# MotorMCU.net
KiCad netlist of a schematic drawn in Altium Designer
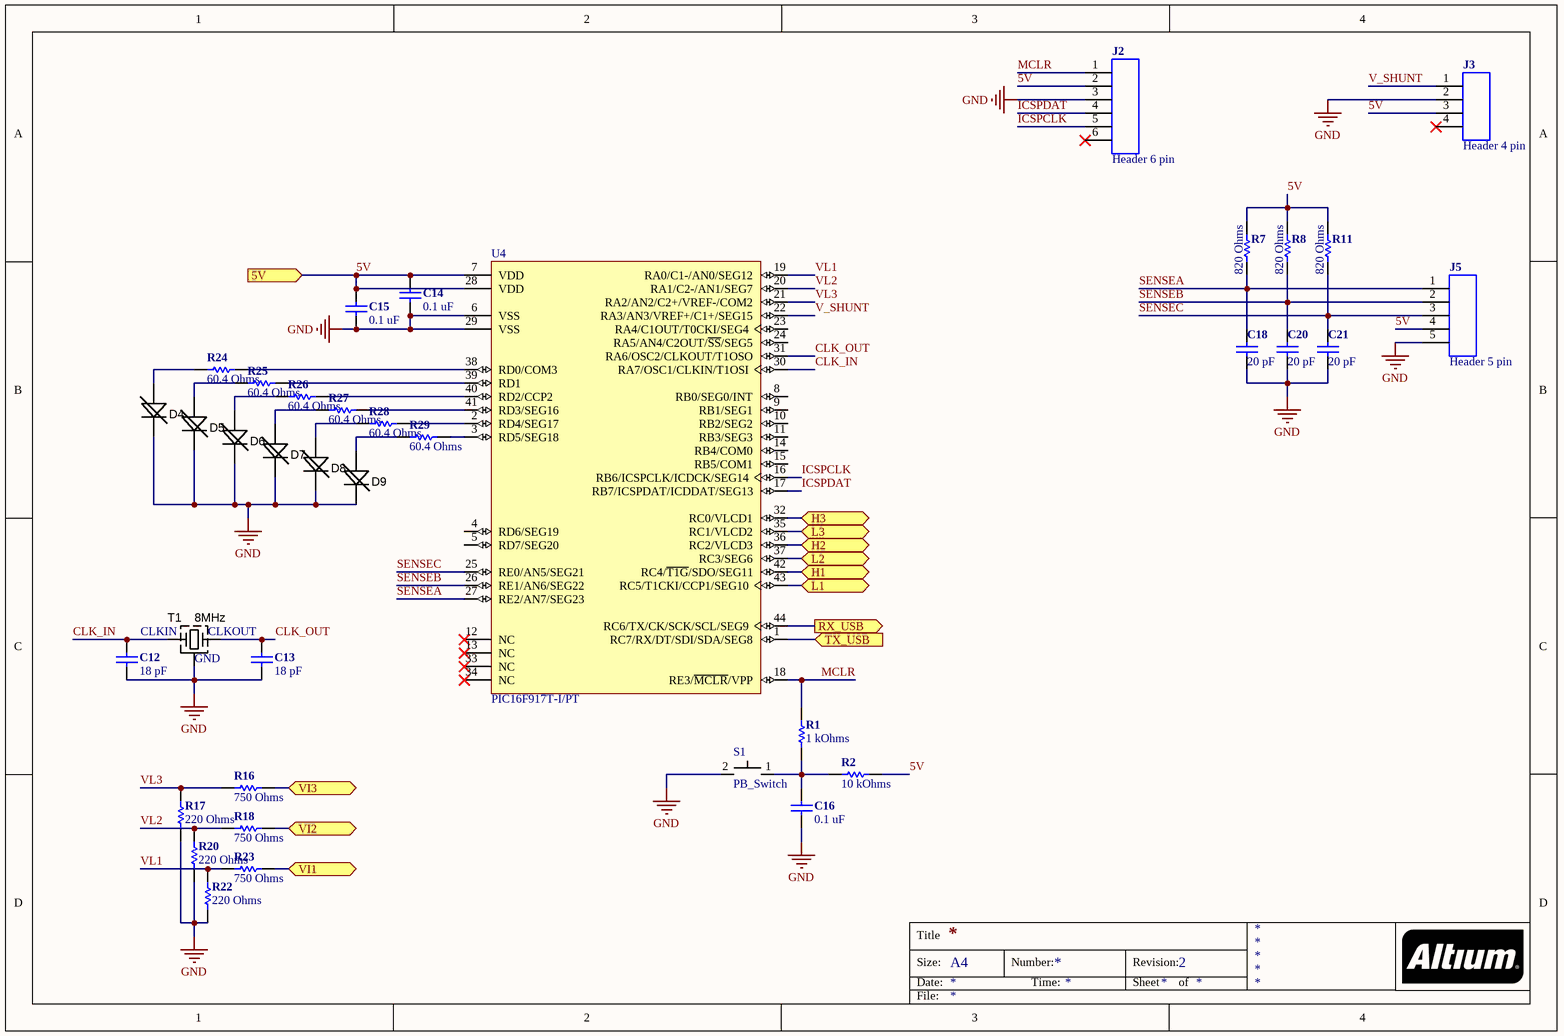
[diagram p0: MotorMCU.SchDoc]

(export (version "E")
  (design (tool "Eeschema 10.0.6"))
  (components
    (comp (ref "C12")
      (value "18 pF")
      (footprint "CAP-0603(1608)-R")
      (description "CAP CER 18 pF 10V 5% C0G 0603")
      (fields (field (name "TOLERANCE") "1 %") (field (name "MANUFACTURER") "Yageo"))
      (libsource (lib "CarlLibrary") (part "CAP- 18 pF- 25 V-CER-0603(1608)"))
    )
    (comp (ref "C13")
      (value "18 pF")
      (footprint "CAP-0603(1608)-R")
      (description "CAP CER 18 pF 10V 5% C0G 0603")
      (fields (field (name "TOLERANCE") "1 %") (field (name "MANUFACTURER") "Yageo"))
      (libsource (lib "CarlLibrary") (part "CAP- 18 pF- 25 V-CER-0603(1608)"))
    )
    (comp (ref "C14")
      (value "0.1 uF")
      (footprint "CAP-0402(1005)-R")
      (description "CAP CER 0.1 UF 16V 5% X7R 0402")
      (fields
        (field (name "MANUFACTURER") "Yageo")
        (field (name "MANUFACTURER PART NUMBER") "CC0402KRX7R7BB104")
      )
      (libsource (lib "CarlLibrary") (part "CAP- 0.1 uF- 16 V-CER-0402(1005)"))
    )
    (comp (ref "C15")
      (value "0.1 uF")
      (footprint "CAP-0402(1005)-R")
      (description "CAP CER 0.1 UF 16V 5% X7R 0402")
      (fields
        (field (name "MANUFACTURER") "Yageo")
        (field (name "MANUFACTURER PART NUMBER") "CC0402KRX7R7BB104")
      )
      (libsource (lib "CarlLibrary") (part "CAP- 0.1 uF- 16 V-CER-0402(1005)"))
    )
    (comp (ref "C16")
      (value "0.1 uF")
      (footprint "CAP-0402(1005)-R")
      (description "CAP CER 0.1 UF 16V 5% X7R 0402")
      (fields (field (name "TOLERANCE") "10 %") (field (name "MANUFACTURER") "Yageo"))
      (libsource (lib "CarlLibrary") (part "CAP- 0.1 uF- 16 V-CER-0402(1005)"))
    )
    (comp (ref "C18")
      (value "20 pF")
      (footprint "CAP-0402(1005)-R")
      (description "CAP CER 20 pF 50V 5% C0G 0402")
      (fields (field (name "TOLERANCE") "5 %") (field (name "MANUFACTURER") "Yageo"))
      (libsource (lib "CarlLibrary") (part "CAP- 20 pF- 50 V-CER-0402(1005)"))
    )
    (comp (ref "C20")
      (value "20 pF")
      (footprint "CAP-0402(1005)-R")
      (description "CAP CER 20 pF 50V 5% C0G 0402")
      (fields (field (name "TOLERANCE") "5 %") (field (name "MANUFACTURER") "Yageo"))
      (libsource (lib "CarlLibrary") (part "CAP- 20 pF- 50 V-CER-0402(1005)"))
    )
    (comp (ref "C21")
      (value "20 pF")
      (footprint "CAP-0402(1005)-R")
      (description "CAP CER 20 pF 50V 5% C0G 0402")
      (fields (field (name "TOLERANCE") "5 %") (field (name "MANUFACTURER") "Yageo"))
      (libsource (lib "CarlLibrary") (part "CAP- 20 pF- 50 V-CER-0402(1005)"))
    )
    (comp (ref "D4")
      (value "Red")
      (footprint "LED-1206")
      (description "LED, 0805 SMD, Red")
      (fields
        (field (name "MANUFACTURER") "Kingbright")
        (field (name "MANUFACTURER PART NUMBER") "APTD3216SURCK")
      )
      (libsource (lib "CarlLibrary") (part "LED_SMD_RED_0805"))
    )
    (comp (ref "D5")
      (value "Red")
      (footprint "LED-1206")
      (description "LED, 0805 SMD, Red")
      (fields
        (field (name "MANUFACTURER") "Kingbright")
        (field (name "MANUFACTURER PART NUMBER") "APTD3216SURCK")
      )
      (libsource (lib "CarlLibrary") (part "LED_SMD_RED_0805"))
    )
    (comp (ref "D6")
      (value "Red")
      (footprint "LED-1206")
      (description "LED, 0805 SMD, Red")
      (fields
        (field (name "MANUFACTURER") "Kingbright")
        (field (name "MANUFACTURER PART NUMBER") "APTD3216SURCK")
      )
      (libsource (lib "CarlLibrary") (part "LED_SMD_RED_0805"))
    )
    (comp (ref "D7")
      (value "Red")
      (footprint "LED-1206")
      (description "LED, 0805 SMD, Red")
      (fields
        (field (name "MANUFACTURER") "Kingbright")
        (field (name "MANUFACTURER PART NUMBER") "APTD3216SURCK")
      )
      (libsource (lib "CarlLibrary") (part "LED_SMD_RED_0805"))
    )
    (comp (ref "D8")
      (value "Red")
      (footprint "LED-1206")
      (description "LED, 0805 SMD, Red")
      (fields
        (field (name "MANUFACTURER") "Kingbright")
        (field (name "MANUFACTURER PART NUMBER") "APTD3216SURCK")
      )
      (libsource (lib "CarlLibrary") (part "LED_SMD_RED_0805"))
    )
    (comp (ref "D9")
      (value "Red")
      (footprint "LED-1206")
      (description "LED, 0805 SMD, Red")
      (fields
        (field (name "MANUFACTURER") "Kingbright")
        (field (name "MANUFACTURER PART NUMBER") "APTD3216SURCK")
      )
      (libsource (lib "CarlLibrary") (part "LED_SMD_RED_0805"))
    )
    (comp (ref "J2")
      (value "Header 6 pin")
      (footprint "HEADER-6-100mil")
      (description "Header, 6 pin, .1 pitch")
      (fields
        (field (name "MANUFACTURER") "TE Connectivity / AMP")
        (field (name "MANUFACTURER PART NUMBER") "4-103327-6")
      )
      (libsource (lib "CarlLibrary") (part "CON-6Pin-100Mil"))
    )
    (comp (ref "J3")
      (value "Header 4 pin")
      (footprint "HEADER-4-100mil")
      (description "Header, 4 pin, .1 pitch")
      (fields (field (name "MANUFACTURER") "Molex") (field (name "MANUFACTURER PART NUMBER") "90136-1104"))
      (libsource (lib "CarlLibrary") (part "CON-4Pin-100Mil"))
    )
    (comp (ref "J5")
      (value "Header 5 pin")
      (footprint "HEADER-5-100mil")
      (description "Header, 5 pin, .1 pitch")
      (fields (field (name "MANUFACTURER") "Molex") (field (name "MANUFACTURER PART NUMBER") "90136-1105"))
      (libsource (lib "CarlLibrary") (part "CON-5Pin-100Mil"))
    )
    (comp (ref "R1")
      (value "1 kOhms")
      (footprint "R-0402(1005)-R")
      (description "RES 1K OHM 62.5 mW 0402(1005) SMD")
      (fields
        (field (name "MANUFACTURER") "Yageo")
        (field (name "MANUFACTURER PART NUMBER") "RC0402JR-071KL")
      )
      (libsource (lib "CarlLibrary") (part "R-1K-62.5 mW-0402(1005)"))
    )
    (comp (ref "R2")
      (value "10 kOhms")
      (footprint "R-0603(1608)-R")
      (description "RES 10k OHM 1/10W 0603 SMD")
      (fields
        (field (name "MANUFACTURER") "Yageo")
        (field (name "MANUFACTURER PART NUMBER") "RC0603FR-0710KL")
      )
      (libsource (lib "CarlLibrary") (part "R-10k-100mW-0603"))
    )
    (comp (ref "R7")
      (value "820 Ohms")
      (footprint "R-0603(1608)-R")
      (description "RES 820 OHM 100 mW 0603(1608) SMD")
      (fields
        (field (name "MANUFACTURER") "Yageo")
        (field (name "MANUFACTURER PART NUMBER") "RT0603DRD07820RL")
      )
      (libsource (lib "CarlLibrary") (part "R-820-100mW-0603(1608)"))
    )
    (comp (ref "R8")
      (value "820 Ohms")
      (footprint "R-0603(1608)-R")
      (description "RES 820 OHM 100 mW 0603(1608) SMD")
      (fields
        (field (name "MANUFACTURER") "Yageo")
        (field (name "MANUFACTURER PART NUMBER") "RT0603DRD07820RL")
      )
      (libsource (lib "CarlLibrary") (part "R-820-100mW-0603(1608)"))
    )
    (comp (ref "R11")
      (value "820 Ohms")
      (footprint "R-0603(1608)-R")
      (description "RES 820 OHM 100 mW 0603(1608) SMD")
      (fields
        (field (name "MANUFACTURER") "Yageo")
        (field (name "MANUFACTURER PART NUMBER") "RT0603DRD07820RL")
      )
      (libsource (lib "CarlLibrary") (part "R-820-100mW-0603(1608)"))
    )
    (comp (ref "R16")
      (value "750 Ohms")
      (footprint "R-0603(1608)-R")
      (description "RES 750 OHM 100 mW 0603(1608) SMD")
      (fields
        (field (name "MANUFACTURER") "Yageo")
        (field (name "MANUFACTURER PART NUMBER") "RT0603DRD07750RL")
      )
      (libsource (lib "CarlLibrary") (part "R-750-100mW-0603(1608)"))
    )
    (comp (ref "R17")
      (value "220 Ohms")
      (footprint "R-0603(1608)-R")
      (description "RES 220 OHM 100 mW 0603(1608) SMD")
      (fields
        (field (name "MANUFACTURER") "Yageo")
        (field (name "MANUFACTURER PART NUMBER") "RT0603FRE07220RL")
      )
      (libsource (lib "CarlLibrary") (part "R-220-100 mW-0603(1608)"))
    )
    (comp (ref "R18")
      (value "750 Ohms")
      (footprint "R-0603(1608)-R")
      (description "RES 750 OHM 100 mW 0603(1608) SMD")
      (fields
        (field (name "MANUFACTURER") "Yageo")
        (field (name "MANUFACTURER PART NUMBER") "RT0603DRD07750RL")
      )
      (libsource (lib "CarlLibrary") (part "R-750-100mW-0603(1608)"))
    )
    (comp (ref "R20")
      (value "220 Ohms")
      (footprint "R-0603(1608)-R")
      (description "RES 220 OHM 100 mW 0603(1608) SMD")
      (fields
        (field (name "MANUFACTURER") "Yageo")
        (field (name "MANUFACTURER PART NUMBER") "RT0603FRE07220RL")
      )
      (libsource (lib "CarlLibrary") (part "R-220-100 mW-0603(1608)"))
    )
    (comp (ref "R22")
      (value "220 Ohms")
      (footprint "R-0603(1608)-R")
      (description "RES 220 OHM 100 mW 0603(1608) SMD")
      (fields
        (field (name "MANUFACTURER") "Yageo")
        (field (name "MANUFACTURER PART NUMBER") "RT0603FRE07220RL")
      )
      (libsource (lib "CarlLibrary") (part "R-220-100 mW-0603(1608)"))
    )
    (comp (ref "R23")
      (value "750 Ohms")
      (footprint "R-0603(1608)-R")
      (description "RES 750 OHM 100 mW 0603(1608) SMD")
      (fields
        (field (name "MANUFACTURER") "Yageo")
        (field (name "MANUFACTURER PART NUMBER") "RT0603DRD07750RL")
      )
      (libsource (lib "CarlLibrary") (part "R-750-100mW-0603(1608)"))
    )
    (comp (ref "R24")
      (value "60.4 Ohms")
      (footprint "R-0603(1608)-R")
      (description "RES 60.4 OHM 100 mW  SMD")
      (fields
        (field (name "MANUFACTURER") "Yageo")
        (field (name "MANUFACTURER PART NUMBER") "RC0603FR-0760R4L")
      )
      (libsource (lib "CarlLibrary") (part "R-60.4-100mW-0805"))
    )
    (comp (ref "R25")
      (value "60.4 Ohms")
      (footprint "R-0603(1608)-R")
      (description "RES 60.4 OHM 100 mW  SMD")
      (fields
        (field (name "MANUFACTURER") "Yageo")
        (field (name "MANUFACTURER PART NUMBER") "RC0603FR-0760R4L")
      )
      (libsource (lib "CarlLibrary") (part "R-60.4-100mW-0805"))
    )
    (comp (ref "R26")
      (value "60.4 Ohms")
      (footprint "R-0603(1608)-R")
      (description "RES 60.4 OHM 100 mW  SMD")
      (fields
        (field (name "MANUFACTURER") "Yageo")
        (field (name "MANUFACTURER PART NUMBER") "RC0603FR-0760R4L")
      )
      (libsource (lib "CarlLibrary") (part "R-60.4-100mW-0805"))
    )
    (comp (ref "R27")
      (value "60.4 Ohms")
      (footprint "R-0603(1608)-R")
      (description "RES 60.4 OHM 100 mW  SMD")
      (fields
        (field (name "MANUFACTURER") "Yageo")
        (field (name "MANUFACTURER PART NUMBER") "RC0603FR-0760R4L")
      )
      (libsource (lib "CarlLibrary") (part "R-60.4-100mW-0805"))
    )
    (comp (ref "R28")
      (value "60.4 Ohms")
      (footprint "R-0603(1608)-R")
      (description "RES 60.4 OHM 100 mW  SMD")
      (fields
        (field (name "MANUFACTURER") "Yageo")
        (field (name "MANUFACTURER PART NUMBER") "RC0603FR-0760R4L")
      )
      (libsource (lib "CarlLibrary") (part "R-60.4-100mW-0805"))
    )
    (comp (ref "R29")
      (value "60.4 Ohms")
      (footprint "R-0603(1608)-R")
      (description "RES 60.4 OHM 100 mW  SMD")
      (fields
        (field (name "MANUFACTURER") "Yageo")
        (field (name "MANUFACTURER PART NUMBER") "RC0603FR-0760R4L")
      )
      (libsource (lib "CarlLibrary") (part "R-60.4-100mW-0805"))
    )
    (comp (ref "S1")
      (value "PB_Switch")
      (footprint "Pushbutton_switches")
      (fields
        (field (name "MANUFACTURER") "TE Connectivity / Alcoswitch")
        (field (name "MANUFACTURER PART NUMBER") "2-1437565-8")
      )
      (libsource (lib "MasterLibrary") (part "PB_Switch"))
    )
    (comp (ref "T1")
      (value "8MHz")
      (footprint "CRYSTAL-8MHZ")
      (description "Oscillator Crystal 8MHz 10ppm")
      (fields
        (field (name "MANUFACTURER") "ABRACON")
        (field (name "MANUFACTURER PART NUMBER") "ABMM2-8.000MHZ-E2-T")
      )
      (libsource (lib "CarlLibrary") (part "CRYSTAL_8MHz"))
    )
    (comp (ref "U4")
      (value "PIC16F917T-I/PT")
      (footprint "TQFP-44")
      (fields
        (field (name "MANUFACTURER") "Microchip Technology")
        (field (name "MANUFACTURER PART NUMBER") "PIC16F917-I/PT")
      )
      (libsource (lib "MasterLibrary") (part "PIC16F917"))
    )
  )
  (nets
    (net (code "1") (name "/5V") (class "Default")
      (node (ref "C14") (pin "1") (pinfunction "1_1") (pintype "passive"))
      (node (ref "C15") (pin "1") (pinfunction "1_1") (pintype "passive"))
      (node (ref "J2") (pin "2") (pinfunction "2_2") (pintype "passive"))
      (node (ref "J3") (pin "3") (pinfunction "3_3") (pintype "passive"))
      (node (ref "J5") (pin "4") (pinfunction "4_4") (pintype "passive"))
      (node (ref "R11") (pin "1") (pinfunction "1_1") (pintype "passive"))
      (node (ref "R2") (pin "2") (pinfunction "2_2") (pintype "passive"))
      (node (ref "R7") (pin "1") (pinfunction "1_1") (pintype "passive"))
      (node (ref "R8") (pin "1") (pinfunction "1_1") (pintype "passive"))
      (node (ref "U4") (pin "28") (pinfunction "VDD_28") (pintype "power_in"))
      (node (ref "U4") (pin "7") (pinfunction "VDD_7") (pintype "power_in"))
    )
    (net (code "2") (name "/CLK_IN") (class "Default")
      (node (ref "C12") (pin "1") (pinfunction "1_1") (pintype "passive"))
      (node (ref "T1") (pin "1") (pinfunction "CLKIN_1") (pintype "passive"))
      (node (ref "U4") (pin "30") (pinfunction "RA7/OSC1/CLKIN/T1OSI_30") (pintype "bidirectional"))
    )
    (net (code "3") (name "/CLK_OUT") (class "Default")
      (node (ref "C13") (pin "1") (pinfunction "1_1") (pintype "passive"))
      (node (ref "T1") (pin "3") (pinfunction "X_3") (pintype "passive"))
      (node (ref "U4") (pin "31") (pinfunction "RA6/OSC2/CLKOUT/T1OSO_31") (pintype "bidirectional"))
    )
    (net (code "4") (name "/H1") (class "Default")
      (node (ref "U4") (pin "42") (pinfunction "RC4/~{T1G}/SDO/SEG11_42") (pintype "bidirectional"))
    )
    (net (code "5") (name "/H2") (class "Default")
      (node (ref "U4") (pin "36") (pinfunction "RC2/VLCD3_36") (pintype "bidirectional"))
    )
    (net (code "6") (name "/H3") (class "Default")
      (node (ref "U4") (pin "32") (pinfunction "RC0/VLCD1_32") (pintype "bidirectional"))
    )
    (net (code "7") (name "/ICSPCLK") (class "Default")
      (node (ref "J2") (pin "5") (pinfunction "5_5") (pintype "passive"))
      (node (ref "U4") (pin "16") (pinfunction "RB6/ICSPCLK/ICDCK/SEG14_16") (pintype "bidirectional"))
    )
    (net (code "8") (name "/ICSPDAT") (class "Default")
      (node (ref "J2") (pin "4") (pinfunction "4_4") (pintype "passive"))
      (node (ref "U4") (pin "17") (pinfunction "RB7/ICSPDAT/ICDDAT/SEG13_17") (pintype "bidirectional"))
    )
    (net (code "9") (name "/L1") (class "Default")
      (node (ref "U4") (pin "43") (pinfunction "RC5/T1CKI/CCP1/SEG10_43") (pintype "bidirectional"))
    )
    (net (code "10") (name "/L2") (class "Default")
      (node (ref "U4") (pin "37") (pinfunction "RC3/SEG6_37") (pintype "bidirectional"))
    )
    (net (code "11") (name "/L3") (class "Default")
      (node (ref "U4") (pin "35") (pinfunction "RC1/VLCD2_35") (pintype "bidirectional"))
    )
    (net (code "12") (name "/MCLR") (class "Default")
      (node (ref "J2") (pin "1") (pinfunction "1_1") (pintype "passive"))
      (node (ref "R1") (pin "1") (pinfunction "1_1") (pintype "passive"))
      (node (ref "U4") (pin "18") (pinfunction "RE3/~{MCLR}/VPP_18") (pintype "bidirectional"))
    )
    (net (code "13") (name "/RX_USB") (class "Default")
      (node (ref "U4") (pin "44") (pinfunction "RC6/TX/CK/SCK/SCL/SEG9_44") (pintype "bidirectional"))
    )
    (net (code "14") (name "/SENSEA") (class "Default")
      (node (ref "C18") (pin "1") (pinfunction "1_1") (pintype "passive"))
      (node (ref "J5") (pin "1") (pinfunction "1_1") (pintype "passive"))
      (node (ref "R7") (pin "2") (pinfunction "2_2") (pintype "passive"))
      (node (ref "U4") (pin "27") (pinfunction "RE2/AN7/SEG23_27") (pintype "bidirectional"))
    )
    (net (code "15") (name "/SENSEB") (class "Default")
      (node (ref "C20") (pin "1") (pinfunction "1_1") (pintype "passive"))
      (node (ref "J5") (pin "2") (pinfunction "2_2") (pintype "passive"))
      (node (ref "R8") (pin "2") (pinfunction "2_2") (pintype "passive"))
      (node (ref "U4") (pin "26") (pinfunction "RE1/AN6/SEG22_26") (pintype "bidirectional"))
    )
    (net (code "16") (name "/SENSEC") (class "Default")
      (node (ref "C21") (pin "1") (pinfunction "1_1") (pintype "passive"))
      (node (ref "J5") (pin "3") (pinfunction "3_3") (pintype "passive"))
      (node (ref "R11") (pin "2") (pinfunction "2_2") (pintype "passive"))
      (node (ref "U4") (pin "25") (pinfunction "RE0/AN5/SEG21_25") (pintype "bidirectional"))
    )
    (net (code "17") (name "/TX_USB") (class "Default")
      (node (ref "U4") (pin "1") (pinfunction "RC7/RX/DT/SDI/SDA/SEG8_1") (pintype "bidirectional"))
    )
    (net (code "18") (name "/VI1") (class "Default")
      (node (ref "R23") (pin "2") (pinfunction "2_2") (pintype "passive"))
    )
    (net (code "19") (name "/VI2") (class "Default")
      (node (ref "R18") (pin "2") (pinfunction "2_2") (pintype "passive"))
    )
    (net (code "20") (name "/VI3") (class "Default")
      (node (ref "R16") (pin "2") (pinfunction "2_2") (pintype "passive"))
    )
    (net (code "21") (name "/VL1") (class "Default")
      (node (ref "R22") (pin "1") (pinfunction "1_1") (pintype "passive"))
      (node (ref "R23") (pin "1") (pinfunction "1_1") (pintype "passive"))
      (node (ref "U4") (pin "19") (pinfunction "RA0/C1-/AN0/SEG12_19") (pintype "bidirectional"))
    )
    (net (code "22") (name "/VL2") (class "Default")
      (node (ref "R18") (pin "1") (pinfunction "1_1") (pintype "passive"))
      (node (ref "R20") (pin "1") (pinfunction "1_1") (pintype "passive"))
      (node (ref "U4") (pin "20") (pinfunction "RA1/C2-/AN1/SEG7_20") (pintype "bidirectional"))
    )
    (net (code "23") (name "/VL3") (class "Default")
      (node (ref "R16") (pin "1") (pinfunction "1_1") (pintype "passive"))
      (node (ref "R17") (pin "1") (pinfunction "1_1") (pintype "passive"))
      (node (ref "U4") (pin "21") (pinfunction "RA2/AN2/C2+/VREF-/COM2_21") (pintype "bidirectional"))
    )
    (net (code "24") (name "/V_SHUNT") (class "Default")
      (node (ref "J3") (pin "1") (pinfunction "1_1") (pintype "passive"))
      (node (ref "U4") (pin "22") (pinfunction "RA3/AN3/VREF+/C1+/SEG15_22") (pintype "bidirectional"))
    )
    (net (code "25") (name "GND") (class "Default")
      (node (ref "C12") (pin "2") (pinfunction "2_2") (pintype "passive"))
      (node (ref "C13") (pin "2") (pinfunction "2_2") (pintype "passive"))
      (node (ref "C14") (pin "2") (pinfunction "2_2") (pintype "passive"))
      (node (ref "C15") (pin "2") (pinfunction "2_2") (pintype "passive"))
      (node (ref "C16") (pin "1") (pinfunction "1_1") (pintype "passive"))
      (node (ref "C18") (pin "2") (pinfunction "2_2") (pintype "passive"))
      (node (ref "C20") (pin "2") (pinfunction "2_2") (pintype "passive"))
      (node (ref "C21") (pin "2") (pinfunction "2_2") (pintype "passive"))
      (node (ref "D4") (pin "K") (pinfunction "K_K") (pintype "passive"))
      (node (ref "D5") (pin "K") (pinfunction "K_K") (pintype "passive"))
      (node (ref "D6") (pin "K") (pinfunction "K_K") (pintype "passive"))
      (node (ref "D7") (pin "K") (pinfunction "K_K") (pintype "passive"))
      (node (ref "D8") (pin "K") (pinfunction "K_K") (pintype "passive"))
      (node (ref "D9") (pin "K") (pinfunction "K_K") (pintype "passive"))
      (node (ref "J2") (pin "3") (pinfunction "3_3") (pintype "passive"))
      (node (ref "J3") (pin "2") (pinfunction "2_2") (pintype "passive"))
      (node (ref "J5") (pin "5") (pinfunction "5_5") (pintype "passive"))
      (node (ref "R17") (pin "2") (pinfunction "2_2") (pintype "passive"))
      (node (ref "R20") (pin "2") (pinfunction "2_2") (pintype "passive"))
      (node (ref "R22") (pin "2") (pinfunction "2_2") (pintype "passive"))
      (node (ref "S1") (pin "2") (pinfunction "2_2") (pintype "passive"))
      (node (ref "T1") (pin "2") (pinfunction "GND_2") (pintype "passive"))
      (node (ref "U4") (pin "29") (pinfunction "VSS_29") (pintype "power_in"))
      (node (ref "U4") (pin "6") (pinfunction "VSS_6") (pintype "power_in"))
    )
    (net (code "26") (name "Net-(C16-Pad2)") (class "Default")
      (node (ref "C16") (pin "2") (pinfunction "2_2") (pintype "passive"))
      (node (ref "R1") (pin "2") (pinfunction "2_2") (pintype "passive"))
      (node (ref "R2") (pin "1") (pinfunction "1_1") (pintype "passive"))
      (node (ref "S1") (pin "1") (pinfunction "1_1") (pintype "passive"))
    )
    (net (code "27") (name "Net-(D4-PadA)") (class "Default")
      (node (ref "D4") (pin "A") (pinfunction "A_A") (pintype "passive"))
      (node (ref "R24") (pin "1") (pinfunction "1_1") (pintype "passive"))
    )
    (net (code "28") (name "Net-(D5-PadA)") (class "Default")
      (node (ref "D5") (pin "A") (pinfunction "A_A") (pintype "passive"))
      (node (ref "R25") (pin "1") (pinfunction "1_1") (pintype "passive"))
    )
    (net (code "29") (name "Net-(D6-PadA)") (class "Default")
      (node (ref "D6") (pin "A") (pinfunction "A_A") (pintype "passive"))
      (node (ref "R26") (pin "1") (pinfunction "1_1") (pintype "passive"))
    )
    (net (code "30") (name "Net-(D7-PadA)") (class "Default")
      (node (ref "D7") (pin "A") (pinfunction "A_A") (pintype "passive"))
      (node (ref "R27") (pin "1") (pinfunction "1_1") (pintype "passive"))
    )
    (net (code "31") (name "Net-(D8-PadA)") (class "Default")
      (node (ref "D8") (pin "A") (pinfunction "A_A") (pintype "passive"))
      (node (ref "R28") (pin "1") (pinfunction "1_1") (pintype "passive"))
    )
    (net (code "32") (name "Net-(D9-PadA)") (class "Default")
      (node (ref "D9") (pin "A") (pinfunction "A_A") (pintype "passive"))
      (node (ref "R29") (pin "1") (pinfunction "1_1") (pintype "passive"))
    )
    (net (code "33") (name "Net-(U4-RD0{slash}COM3)") (class "Default")
      (node (ref "R24") (pin "2") (pinfunction "2_2") (pintype "passive"))
      (node (ref "U4") (pin "38") (pinfunction "RD0/COM3_38") (pintype "bidirectional"))
    )
    (net (code "34") (name "Net-(U4-RD1)") (class "Default")
      (node (ref "R25") (pin "2") (pinfunction "2_2") (pintype "passive"))
      (node (ref "U4") (pin "39") (pinfunction "RD1_39") (pintype "bidirectional"))
    )
    (net (code "35") (name "Net-(U4-RD2{slash}CCP2)") (class "Default")
      (node (ref "R26") (pin "2") (pinfunction "2_2") (pintype "passive"))
      (node (ref "U4") (pin "40") (pinfunction "RD2/CCP2_40") (pintype "bidirectional"))
    )
    (net (code "36") (name "Net-(U4-RD3{slash}SEG16)") (class "Default")
      (node (ref "R27") (pin "2") (pinfunction "2_2") (pintype "passive"))
      (node (ref "U4") (pin "41") (pinfunction "RD3/SEG16_41") (pintype "bidirectional"))
    )
    (net (code "37") (name "Net-(U4-RD4{slash}SEG17)") (class "Default")
      (node (ref "R28") (pin "2") (pinfunction "2_2") (pintype "passive"))
      (node (ref "U4") (pin "2") (pinfunction "RD4/SEG17_2") (pintype "bidirectional"))
    )
    (net (code "38") (name "Net-(U4-RD5{slash}SEG18)") (class "Default")
      (node (ref "R29") (pin "2") (pinfunction "2_2") (pintype "passive"))
      (node (ref "U4") (pin "3") (pinfunction "RD5/SEG18_3") (pintype "bidirectional"))
    )
    (net (code "39") (name "unconnected-(J2-Pad6)") (class "Default")
      (node (ref "J2") (pin "6") (pinfunction "6_6") (pintype "passive+no_connect"))
    )
    (net (code "40") (name "unconnected-(J3-Pad4)") (class "Default")
      (node (ref "J3") (pin "4") (pinfunction "4_4") (pintype "passive+no_connect"))
    )
    (net (code "41") (name "unconnected-(U4-NC-Pad12)") (class "Default")
      (node (ref "U4") (pin "12") (pinfunction "NC_12") (pintype "passive+no_connect"))
    )
    (net (code "42") (name "unconnected-(U4-NC-Pad13)") (class "Default")
      (node (ref "U4") (pin "13") (pinfunction "NC_13") (pintype "passive+no_connect"))
    )
    (net (code "43") (name "unconnected-(U4-NC-Pad33)") (class "Default")
      (node (ref "U4") (pin "33") (pinfunction "NC_33") (pintype "passive+no_connect"))
    )
    (net (code "44") (name "unconnected-(U4-NC-Pad34)") (class "Default")
      (node (ref "U4") (pin "34") (pinfunction "NC_34") (pintype "passive+no_connect"))
    )
    (net (code "45") (name "unconnected-(U4-RA4{slash}C1OUT{slash}T0CKI{slash}SEG4-Pad23)") (class "Default")
      (node (ref "U4") (pin "23") (pinfunction "RA4/C1OUT/T0CKI/SEG4_23") (pintype "bidirectional"))
    )
    (net (code "46") (name "unconnected-(U4-RA5{slash}AN4{slash}C2OUT{slash}~{SS}{slash}SEG5-Pad24)") (class "Default")
      (node (ref "U4") (pin "24") (pinfunction "RA5/AN4/C2OUT/~{SS}/SEG5_24") (pintype "bidirectional"))
    )
    (net (code "47") (name "unconnected-(U4-RB0{slash}SEG0{slash}INT-Pad8)") (class "Default")
      (node (ref "U4") (pin "8") (pinfunction "RB0/SEG0/INT_8") (pintype "bidirectional"))
    )
    (net (code "48") (name "unconnected-(U4-RB1{slash}SEG1-Pad9)") (class "Default")
      (node (ref "U4") (pin "9") (pinfunction "RB1/SEG1_9") (pintype "bidirectional"))
    )
    (net (code "49") (name "unconnected-(U4-RB2{slash}SEG2-Pad10)") (class "Default")
      (node (ref "U4") (pin "10") (pinfunction "RB2/SEG2_10") (pintype "bidirectional"))
    )
    (net (code "50") (name "unconnected-(U4-RB3{slash}SEG3-Pad11)") (class "Default")
      (node (ref "U4") (pin "11") (pinfunction "RB3/SEG3_11") (pintype "bidirectional"))
    )
    (net (code "51") (name "unconnected-(U4-RB4{slash}COM0-Pad14)") (class "Default")
      (node (ref "U4") (pin "14") (pinfunction "RB4/COM0_14") (pintype "bidirectional"))
    )
    (net (code "52") (name "unconnected-(U4-RB5{slash}COM1-Pad15)") (class "Default")
      (node (ref "U4") (pin "15") (pinfunction "RB5/COM1_15") (pintype "bidirectional"))
    )
    (net (code "53") (name "unconnected-(U4-RD6{slash}SEG19-Pad4)") (class "Default")
      (node (ref "U4") (pin "4") (pinfunction "RD6/SEG19_4") (pintype "bidirectional"))
    )
    (net (code "54") (name "unconnected-(U4-RD7{slash}SEG20-Pad5)") (class "Default")
      (node (ref "U4") (pin "5") (pinfunction "RD7/SEG20_5") (pintype "bidirectional"))
    )
  )
)
